# Power_Management.net
KiCad netlist of a schematic drawn in Altium Designer
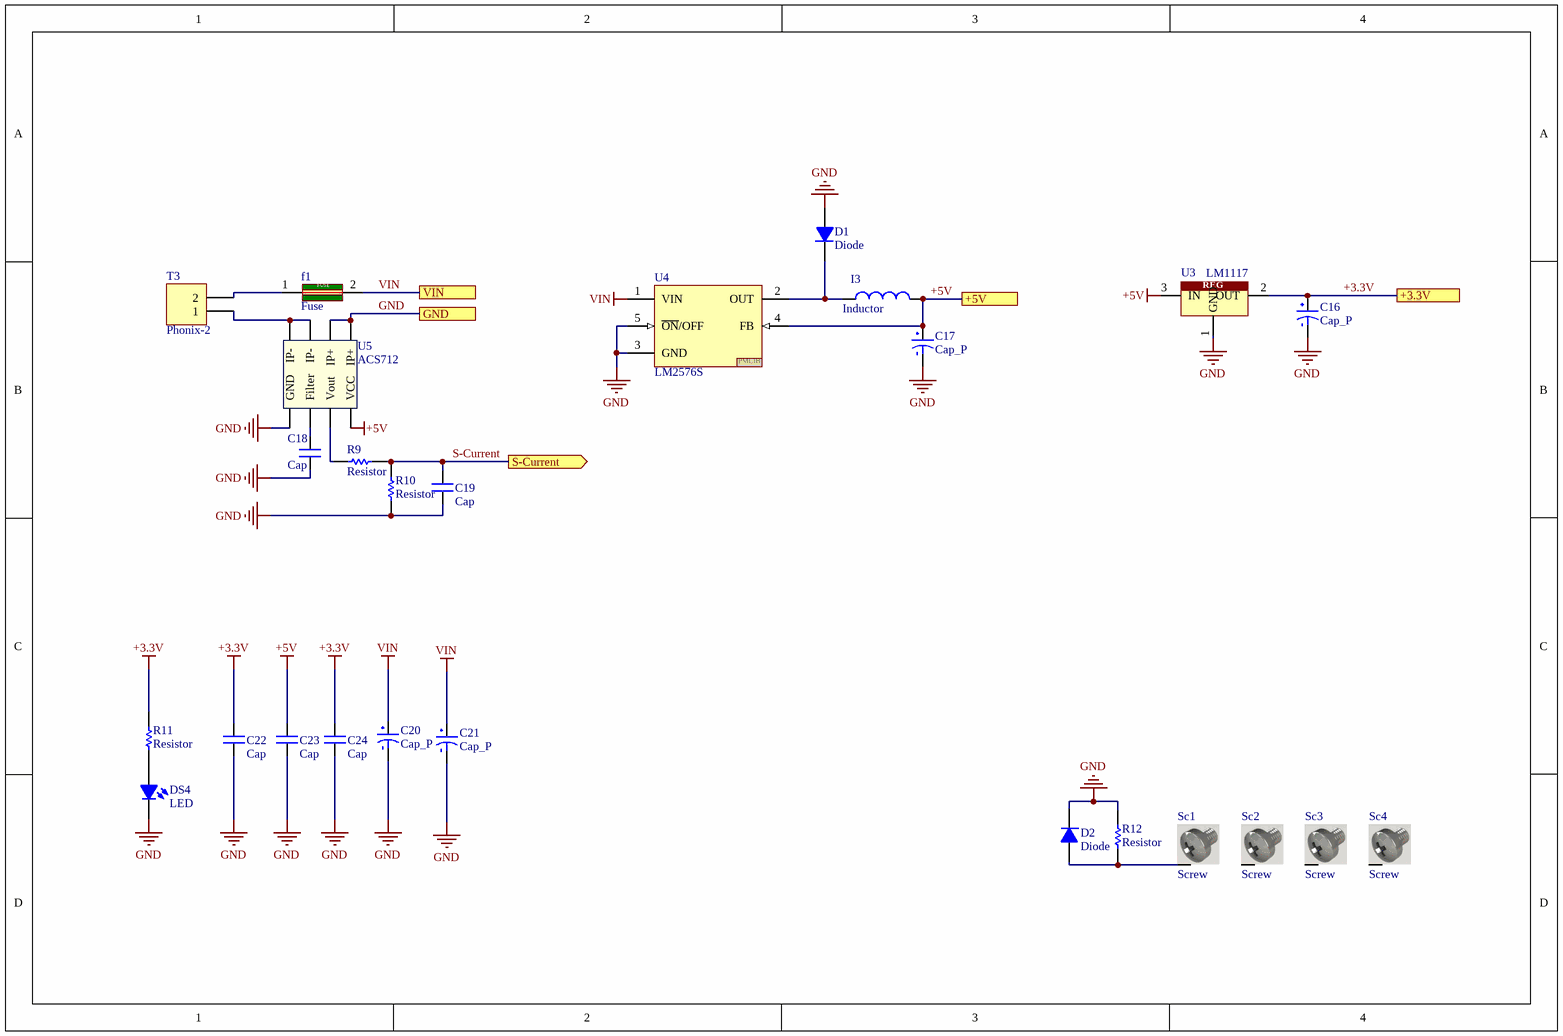
[diagram p0: Power Management.SchDoc]

(export (version "E")
  (design (tool "Eeschema 10.0.6"))
  (components
    (comp (ref "C16")
      (value "Cap_P")
      (footprint "Cap_4mm")
      (description "Polarity")
      (libsource (lib "PMLIB2020") (part "Cap_P"))
    )
    (comp (ref "C17")
      (value "Cap_P")
      (footprint "Cap_4mm")
      (description "Polarity")
      (libsource (lib "PMLIB2020") (part "Cap_P"))
    )
    (comp (ref "C18")
      (value "Cap")
      (footprint "Cap0805")
      (description "Surface mount Capacitor")
      (libsource (lib "PMLIB2020") (part "Cap"))
    )
    (comp (ref "C19")
      (value "Cap")
      (footprint "Cap0805")
      (description "Surface mount Capacitor")
      (libsource (lib "PMLIB2020") (part "Cap"))
    )
    (comp (ref "C20")
      (value "Cap_P")
      (footprint "Cap_5mm")
      (description "Polarity")
      (libsource (lib "PMLIB2020") (part "Cap_P"))
    )
    (comp (ref "C21")
      (value "Cap_P")
      (footprint "Cap_5mm")
      (description "Polarity")
      (libsource (lib "PMLIB2020") (part "Cap_P"))
    )
    (comp (ref "C22")
      (value "Cap")
      (footprint "Cap0805")
      (description "Surface mount Capacitor")
      (libsource (lib "PMLIB2020") (part "Cap"))
    )
    (comp (ref "C23")
      (value "Cap")
      (footprint "Cap0805")
      (description "Surface mount Capacitor")
      (libsource (lib "PMLIB2020") (part "Cap"))
    )
    (comp (ref "C24")
      (value "Cap")
      (footprint "Cap0805")
      (description "Surface mount Capacitor")
      (libsource (lib "PMLIB2020") (part "Cap"))
    )
    (comp (ref "D1") (value "Diode") (footprint "Diod-1A-SMD") (libsource (lib "PMLIB2020") (part "Diode")))
    (comp (ref "D2") (value "Diode") (footprint "Diod-1A-SMD") (libsource (lib "PMLIB2020") (part "Diode")))
    (comp (ref "DS4") (value "LED") (footprint "Led0805") (libsource (lib "PMLIB2020") (part "LED")))
    (comp (ref "f1") (value "Fuse") (footprint "1206") (libsource (lib "PMLIB2020") (part "Fuse")))
    (comp (ref "I3")
      (value "Inductor")
      (footprint "Indicator_SMD")
      (description "Indicator")
      (libsource (lib "PMLIB2020") (part "Inductor"))
    )
    (comp (ref "R9") (value "Resistor") (footprint "R0805") (libsource (lib "PMLIB2020") (part "Resistor")))
    (comp (ref "R10") (value "Resistor") (footprint "R0805") (libsource (lib "PMLIB2020") (part "Resistor")))
    (comp (ref "R11") (value "Resistor") (footprint "R0805") (libsource (lib "PMLIB2020") (part "Resistor")))
    (comp (ref "R12") (value "Resistor") (footprint "0603") (libsource (lib "PMLIB2020") (part "Resistor")))
    (comp (ref "Sc1")
      (value "Screw")
      (footprint "Screw")
      (description "Screw 3mm")
      (libsource (lib "PMLIB2020") (part "Screw"))
    )
    (comp (ref "Sc2")
      (value "Screw")
      (footprint "Screw")
      (description "Screw 3mm")
      (libsource (lib "PMLIB2020") (part "Screw"))
    )
    (comp (ref "Sc3")
      (value "Screw")
      (footprint "Screw")
      (description "Screw 3mm")
      (libsource (lib "PMLIB2020") (part "Screw"))
    )
    (comp (ref "Sc4")
      (value "Screw")
      (footprint "Screw")
      (description "Screw 3mm")
      (libsource (lib "PMLIB2020") (part "Screw"))
    )
    (comp (ref "T3")
      (value "Phonix-2")
      (footprint "Phonix-2")
      (description "Connector")
      (libsource (lib "PMLIB2020") (part "Phonix-2"))
    )
    (comp (ref "U3")
      (value "LM1117")
      (footprint "DPACK")
      (description "Regulator")
      (libsource (lib "PMLIB2020") (part "LM1117"))
    )
    (comp (ref "U4")
      (value "LM2576S")
      (footprint "LM2576S")
      (description "Regulator")
      (libsource (lib "PMLIB2020") (part "LM2576S"))
    )
    (comp (ref "U5")
      (value "ACS712")
      (footprint "SOP8")
      (description "Hall effect Current Sensor")
      (libsource (lib "PMLIB2020") (part "ACS712"))
    )
  )
  (nets
    (net (code "1") (name "+3.3V") (class "Default")
      (node (ref "C16") (pin "2") (pinfunction "2_2") (pintype "passive"))
      (node (ref "C22") (pin "2") (pinfunction "2_2") (pintype "passive"))
      (node (ref "C24") (pin "2") (pinfunction "2_2") (pintype "passive"))
      (node (ref "R11") (pin "1") (pinfunction "1_1") (pintype "passive"))
      (node (ref "U3") (pin "2") (pinfunction "OUT_2") (pintype "passive"))
    )
    (net (code "2") (name "+5V") (class "Default")
      (node (ref "C17") (pin "2") (pinfunction "2_2") (pintype "passive"))
      (node (ref "C23") (pin "2") (pinfunction "2_2") (pintype "passive"))
      (node (ref "I3") (pin "2") (pinfunction "2_2") (pintype "passive"))
      (node (ref "U3") (pin "3") (pinfunction "IN_3") (pintype "passive"))
      (node (ref "U4") (pin "4") (pinfunction "FB_4") (pintype "input"))
      (node (ref "U5") (pin "8") (pinfunction "VCC_8") (pintype "passive"))
    )
    (net (code "3") (name "/S-Current") (class "Default")
      (node (ref "C19") (pin "2") (pinfunction "2_2") (pintype "passive"))
      (node (ref "R10") (pin "1") (pinfunction "1_1") (pintype "passive"))
      (node (ref "R9") (pin "1") (pinfunction "1_1") (pintype "passive"))
    )
    (net (code "4") (name "GND") (class "Default")
      (node (ref "C16") (pin "1") (pinfunction "1_1") (pintype "passive"))
      (node (ref "C17") (pin "1") (pinfunction "1_1") (pintype "passive"))
      (node (ref "C18") (pin "1") (pinfunction "1_1") (pintype "passive"))
      (node (ref "C19") (pin "1") (pinfunction "1_1") (pintype "passive"))
      (node (ref "C20") (pin "1") (pinfunction "1_1") (pintype "passive"))
      (node (ref "C21") (pin "1") (pinfunction "1_1") (pintype "passive"))
      (node (ref "C22") (pin "1") (pinfunction "1_1") (pintype "passive"))
      (node (ref "C23") (pin "1") (pinfunction "1_1") (pintype "passive"))
      (node (ref "C24") (pin "1") (pinfunction "1_1") (pintype "passive"))
      (node (ref "D1") (pin "A") (pinfunction "A_A") (pintype "passive"))
      (node (ref "D2") (pin "K") (pinfunction "K_K") (pintype "passive"))
      (node (ref "DS4") (pin "K") (pinfunction "K_K") (pintype "passive"))
      (node (ref "R10") (pin "2") (pinfunction "2_2") (pintype "passive"))
      (node (ref "R12") (pin "1") (pinfunction "1_1") (pintype "passive"))
      (node (ref "U3") (pin "1") (pinfunction "GND_1") (pintype "passive"))
      (node (ref "U4") (pin "3") (pinfunction "GND_3") (pintype "power_in"))
      (node (ref "U4") (pin "5") (pinfunction "~{ON}/OFF_5") (pintype "input"))
      (node (ref "U5") (pin "1") (pinfunction "IP+_1") (pintype "passive"))
      (node (ref "U5") (pin "2") (pinfunction "IP+_2") (pintype "passive"))
      (node (ref "U5") (pin "5") (pinfunction "GND_5") (pintype "passive"))
    )
    (net (code "5") (name "Net-(D2-PadA)") (class "Default")
      (node (ref "D2") (pin "A") (pinfunction "A_A") (pintype "passive"))
      (node (ref "R12") (pin "2") (pinfunction "2_2") (pintype "passive"))
      (node (ref "Sc1") (pin "S") (pinfunction "S_S") (pintype "passive"))
    )
    (net (code "6") (name "Net-(DS4-PadA)") (class "Default")
      (node (ref "DS4") (pin "A") (pinfunction "A_A") (pintype "passive"))
      (node (ref "R11") (pin "2") (pinfunction "2_2") (pintype "passive"))
    )
    (net (code "7") (name "Net-(T3-Pad1)") (class "Default")
      (node (ref "T3") (pin "1") (pinfunction "1_1") (pintype "passive"))
      (node (ref "U5") (pin "3") (pinfunction "IP-_3") (pintype "passive"))
      (node (ref "U5") (pin "4") (pinfunction "IP-_4") (pintype "passive"))
    )
    (net (code "8") (name "Net-(U4-OUT)") (class "Default")
      (node (ref "D1") (pin "K") (pinfunction "K_K") (pintype "passive"))
      (node (ref "I3") (pin "1") (pinfunction "1_1") (pintype "passive"))
      (node (ref "U4") (pin "2") (pinfunction "OUT_2") (pintype "power_in"))
    )
    (net (code "9") (name "Net-(U5-Filter)") (class "Default")
      (node (ref "C18") (pin "2") (pinfunction "2_2") (pintype "passive"))
      (node (ref "U5") (pin "6") (pinfunction "Filter_6") (pintype "passive"))
    )
    (net (code "10") (name "Net-(U5-Vout)") (class "Default")
      (node (ref "R9") (pin "2") (pinfunction "2_2") (pintype "passive"))
      (node (ref "U5") (pin "7") (pinfunction "Vout_7") (pintype "passive"))
    )
    (net (code "11") (name "Net-(f1-IN)") (class "Default")
      (node (ref "T3") (pin "2") (pinfunction "2_2") (pintype "passive"))
      (node (ref "f1") (pin "1") (pinfunction "IN_1") (pintype "passive"))
    )
    (net (code "12") (name "VIN") (class "Default")
      (node (ref "C20") (pin "2") (pinfunction "2_2") (pintype "passive"))
      (node (ref "C21") (pin "2") (pinfunction "2_2") (pintype "passive"))
      (node (ref "U4") (pin "1") (pinfunction "VIN_1") (pintype "power_in"))
      (node (ref "f1") (pin "2") (pinfunction "OUT_2") (pintype "passive"))
    )
    (net (code "13") (name "unconnected-(Sc2-PadS)") (class "Default")
      (node (ref "Sc2") (pin "S") (pinfunction "S_S") (pintype "passive"))
    )
    (net (code "14") (name "unconnected-(Sc3-PadS)") (class "Default")
      (node (ref "Sc3") (pin "S") (pinfunction "S_S") (pintype "passive"))
    )
    (net (code "15") (name "unconnected-(Sc4-PadS)") (class "Default")
      (node (ref "Sc4") (pin "S") (pinfunction "S_S") (pintype "passive"))
    )
  )
)
